# power.net
KiCad netlist of a schematic drawn in EAGLE
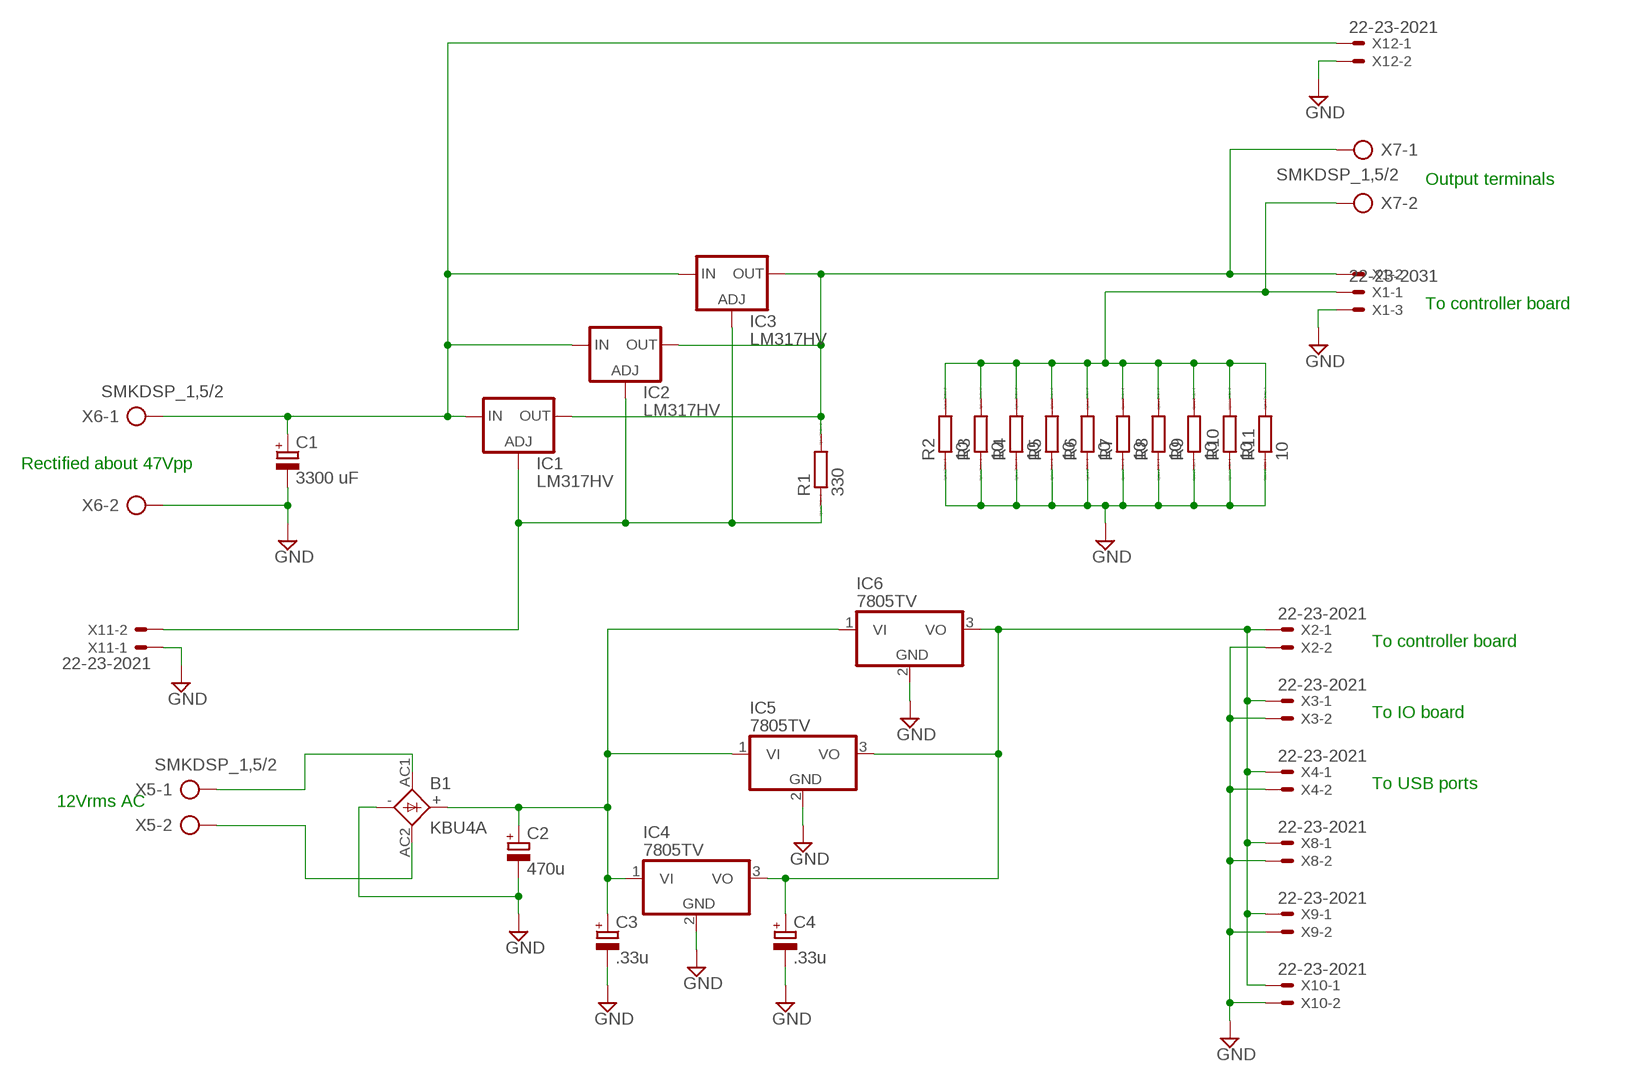
[diagram p0: schematic, sheet 1]

(export (version "E")
  (design (tool "Eeschema 10.0.6"))
  (components
    (comp (ref "B1")
      (value "KBU4A")
      (footprint "eagle-import:2KBB-R")
      (libsource (lib "eagle-import") (part "2KBB-R"))
    )
    (comp (ref "C1")
      (value "3300 uF")
      (footprint "eagle-import:EB25D")
      (libsource (lib "eagle-import") (part "CPOL-EUE10-25"))
    )
    (comp (ref "C2")
      (value "470u")
      (footprint "eagle-import:E5-10,5")
      (libsource (lib "eagle-import") (part "CPOL-EUE5-10.5"))
    )
    (comp (ref "C3")
      (value ".33u")
      (footprint "eagle-import:E2-5")
      (libsource (lib "eagle-import") (part "CPOL-EUE2-5"))
    )
    (comp (ref "C4")
      (value ".33u")
      (footprint "eagle-import:E2-5")
      (libsource (lib "eagle-import") (part "CPOL-EUE2-5"))
    )
    (comp (ref "IC1")
      (value "LM317HV")
      (footprint "eagle-import:317TS")
      (libsource (lib "eagle-import") (part "LM317TS"))
    )
    (comp (ref "IC2")
      (value "LM317HV")
      (footprint "eagle-import:317TS")
      (libsource (lib "eagle-import") (part "LM317TS"))
    )
    (comp (ref "IC3")
      (value "LM317HV")
      (footprint "eagle-import:317TS")
      (libsource (lib "eagle-import") (part "LM317TS"))
    )
    (comp (ref "IC4")
      (value "7805TV")
      (footprint "eagle-import:TO220V")
      (libsource (lib "eagle-import") (part "78TV05"))
    )
    (comp (ref "IC5")
      (value "7805TV")
      (footprint "eagle-import:TO220V")
      (libsource (lib "eagle-import") (part "78TV05"))
    )
    (comp (ref "IC6")
      (value "7805TV")
      (footprint "eagle-import:TO220V")
      (libsource (lib "eagle-import") (part "78TV05"))
    )
    (comp (ref "R1")
      (value "330")
      (footprint "eagle-import:0207_7")
      (libsource (lib "eagle-import") (part "R-EU_0207_7"))
    )
    (comp (ref "R2")
      (value "10")
      (footprint "eagle-import:0204_7")
      (libsource (lib "eagle-import") (part "R-EU_0204_7"))
    )
    (comp (ref "R3")
      (value "10")
      (footprint "eagle-import:0204_7")
      (libsource (lib "eagle-import") (part "R-EU_0204_7"))
    )
    (comp (ref "R4")
      (value "10")
      (footprint "eagle-import:0204_7")
      (libsource (lib "eagle-import") (part "R-EU_0204_7"))
    )
    (comp (ref "R5")
      (value "10")
      (footprint "eagle-import:0204_7")
      (libsource (lib "eagle-import") (part "R-EU_0204_7"))
    )
    (comp (ref "R6")
      (value "10")
      (footprint "eagle-import:0204_7")
      (libsource (lib "eagle-import") (part "R-EU_0204_7"))
    )
    (comp (ref "R7")
      (value "10")
      (footprint "eagle-import:0204_7")
      (libsource (lib "eagle-import") (part "R-EU_0204_7"))
    )
    (comp (ref "R8")
      (value "10")
      (footprint "eagle-import:0204_7")
      (libsource (lib "eagle-import") (part "R-EU_0204_7"))
    )
    (comp (ref "R9")
      (value "10")
      (footprint "eagle-import:0204_7")
      (libsource (lib "eagle-import") (part "R-EU_0204_7"))
    )
    (comp (ref "R10")
      (value "10")
      (footprint "eagle-import:0204_7")
      (libsource (lib "eagle-import") (part "R-EU_0204_7"))
    )
    (comp (ref "R11")
      (value "10")
      (footprint "eagle-import:0204_7")
      (libsource (lib "eagle-import") (part "R-EU_0204_7"))
    )
    (comp (ref "X1")
      (value "22-23-2031")
      (footprint "eagle-import:22-23-2031")
      (fields (field (name "MF") "MOLEX"))
      (libsource (lib "eagle-import") (part "22-23-2031"))
    )
    (comp (ref "X2")
      (value "22-23-2021")
      (footprint "eagle-import:22-23-2021")
      (fields (field (name "MF") "MOLEX"))
      (libsource (lib "eagle-import") (part "22-23-2021"))
    )
    (comp (ref "X3")
      (value "22-23-2021")
      (footprint "eagle-import:22-23-2021")
      (fields (field (name "MF") "MOLEX"))
      (libsource (lib "eagle-import") (part "22-23-2021"))
    )
    (comp (ref "X4")
      (value "22-23-2021")
      (footprint "eagle-import:22-23-2021")
      (fields (field (name "MF") "MOLEX"))
      (libsource (lib "eagle-import") (part "22-23-2021"))
    )
    (comp (ref "X5")
      (value "SMKDSP_1,5/2")
      (footprint "eagle-import:SMKDSP_1,5_2")
      (fields (field (name "MF") "FARNELL") (field (name "MPN") "1733570"))
      (libsource (lib "eagle-import") (part "SMKDSP_1,5/2"))
    )
    (comp (ref "X6")
      (value "SMKDSP_1,5/2")
      (footprint "eagle-import:SMKDSP_1,5_2")
      (fields (field (name "MF") "FARNELL") (field (name "MPN") "1733570"))
      (libsource (lib "eagle-import") (part "SMKDSP_1,5/2"))
    )
    (comp (ref "X7")
      (value "SMKDSP_1,5/2")
      (footprint "eagle-import:SMKDSP_1,5_2")
      (fields (field (name "MF") "FARNELL") (field (name "MPN") "1733570"))
      (libsource (lib "eagle-import") (part "SMKDSP_1,5/2"))
    )
    (comp (ref "X8")
      (value "22-23-2021")
      (footprint "eagle-import:22-23-2021")
      (fields (field (name "MF") "MOLEX"))
      (libsource (lib "eagle-import") (part "22-23-2021"))
    )
    (comp (ref "X9")
      (value "22-23-2021")
      (footprint "eagle-import:22-23-2021")
      (fields (field (name "MF") "MOLEX"))
      (libsource (lib "eagle-import") (part "22-23-2021"))
    )
    (comp (ref "X10")
      (value "22-23-2021")
      (footprint "eagle-import:22-23-2021")
      (fields (field (name "MF") "MOLEX"))
      (libsource (lib "eagle-import") (part "22-23-2021"))
    )
    (comp (ref "X11")
      (value "22-23-2021")
      (footprint "eagle-import:22-23-2021")
      (fields (field (name "MF") "MOLEX"))
      (libsource (lib "eagle-import") (part "22-23-2021"))
    )
    (comp (ref "X12")
      (value "22-23-2021")
      (footprint "eagle-import:22-23-2021")
      (fields (field (name "MF") "MOLEX"))
      (libsource (lib "eagle-import") (part "22-23-2021"))
    )
  )
  (nets
    (net (code "1") (name "GND") (class "Default")
      (node (ref "B1") (pin "-") (pinfunction "-_-") (pintype "passive"))
      (node (ref "C1") (pin "-") (pinfunction "-_-") (pintype "passive"))
      (node (ref "C2") (pin "-") (pinfunction "-_-") (pintype "passive"))
      (node (ref "C3") (pin "-") (pinfunction "-_-") (pintype "passive"))
      (node (ref "C4") (pin "-") (pinfunction "-_-") (pintype "passive"))
      (node (ref "IC4") (pin "2") (pinfunction "GND_2") (pintype "passive"))
      (node (ref "IC5") (pin "2") (pinfunction "GND_2") (pintype "passive"))
      (node (ref "IC6") (pin "2") (pinfunction "GND_2") (pintype "passive"))
      (node (ref "R10") (pin "1") (pinfunction "1_1") (pintype "passive"))
      (node (ref "R11") (pin "1") (pinfunction "1_1") (pintype "passive"))
      (node (ref "R2") (pin "1") (pinfunction "1_1") (pintype "passive"))
      (node (ref "R3") (pin "1") (pinfunction "1_1") (pintype "passive"))
      (node (ref "R4") (pin "1") (pinfunction "1_1") (pintype "passive"))
      (node (ref "R5") (pin "1") (pinfunction "1_1") (pintype "passive"))
      (node (ref "R6") (pin "1") (pinfunction "1_1") (pintype "passive"))
      (node (ref "R7") (pin "1") (pinfunction "1_1") (pintype "passive"))
      (node (ref "R8") (pin "1") (pinfunction "1_1") (pintype "passive"))
      (node (ref "R9") (pin "1") (pinfunction "1_1") (pintype "passive"))
      (node (ref "X1") (pin "3") (pinfunction "S_3") (pintype "passive"))
      (node (ref "X10") (pin "2") (pinfunction "S_2") (pintype "passive"))
      (node (ref "X11") (pin "1") (pinfunction "S_1") (pintype "passive"))
      (node (ref "X12") (pin "2") (pinfunction "S_2") (pintype "passive"))
      (node (ref "X2") (pin "2") (pinfunction "S_2") (pintype "passive"))
      (node (ref "X3") (pin "2") (pinfunction "S_2") (pintype "passive"))
      (node (ref "X4") (pin "2") (pinfunction "S_2") (pintype "passive"))
      (node (ref "X6") (pin "2") (pinfunction "KL_2") (pintype "passive"))
      (node (ref "X8") (pin "2") (pinfunction "S_2") (pintype "passive"))
      (node (ref "X9") (pin "2") (pinfunction "S_2") (pintype "passive"))
    )
    (net (code "2") (name "Net-(IC1-ADJ)") (class "Default")
      (node (ref "IC1") (pin "1") (pinfunction "ADJ_1") (pintype "input"))
      (node (ref "IC2") (pin "1") (pinfunction "ADJ_1") (pintype "input"))
      (node (ref "IC3") (pin "1") (pinfunction "ADJ_1") (pintype "input"))
      (node (ref "R1") (pin "1") (pinfunction "1_1") (pintype "passive"))
      (node (ref "X11") (pin "2") (pinfunction "S_2") (pintype "passive"))
    )
    (net (code "3") (name "Net-(IC1-IN)") (class "Default")
      (node (ref "C1") (pin "+") (pinfunction "+_+") (pintype "passive"))
      (node (ref "IC1") (pin "3") (pinfunction "IN_3") (pintype "input"))
      (node (ref "IC2") (pin "3") (pinfunction "IN_3") (pintype "input"))
      (node (ref "IC3") (pin "3") (pinfunction "IN_3") (pintype "input"))
      (node (ref "X12") (pin "1") (pinfunction "S_1") (pintype "passive"))
      (node (ref "X6") (pin "1") (pinfunction "KL_1") (pintype "passive"))
    )
    (net (code "4") (name "Net-(IC1-OUT)") (class "Default")
      (node (ref "IC1") (pin "2") (pinfunction "OUT_2") (pintype "passive"))
      (node (ref "IC2") (pin "2") (pinfunction "OUT_2") (pintype "passive"))
      (node (ref "IC3") (pin "2") (pinfunction "OUT_2") (pintype "passive"))
      (node (ref "R1") (pin "2") (pinfunction "2_2") (pintype "passive"))
      (node (ref "X1") (pin "2") (pinfunction "S_2") (pintype "passive"))
      (node (ref "X7") (pin "1") (pinfunction "KL_1") (pintype "passive"))
    )
    (net (code "5") (name "Net-(IC4-VI)") (class "Default")
      (node (ref "B1") (pin "+") (pinfunction "+_+") (pintype "passive"))
      (node (ref "C2") (pin "+") (pinfunction "+_+") (pintype "passive"))
      (node (ref "C3") (pin "+") (pinfunction "+_+") (pintype "passive"))
      (node (ref "IC4") (pin "1") (pinfunction "VI_1") (pintype "input"))
      (node (ref "IC5") (pin "1") (pinfunction "VI_1") (pintype "input"))
      (node (ref "IC6") (pin "1") (pinfunction "VI_1") (pintype "input"))
    )
    (net (code "6") (name "Net-(IC4-VO)") (class "Default")
      (node (ref "C4") (pin "+") (pinfunction "+_+") (pintype "passive"))
      (node (ref "IC4") (pin "3") (pinfunction "VO_3") (pintype "passive"))
      (node (ref "IC5") (pin "3") (pinfunction "VO_3") (pintype "passive"))
      (node (ref "IC6") (pin "3") (pinfunction "VO_3") (pintype "passive"))
      (node (ref "X10") (pin "1") (pinfunction "S_1") (pintype "passive"))
      (node (ref "X2") (pin "1") (pinfunction "S_1") (pintype "passive"))
      (node (ref "X3") (pin "1") (pinfunction "S_1") (pintype "passive"))
      (node (ref "X4") (pin "1") (pinfunction "S_1") (pintype "passive"))
      (node (ref "X8") (pin "1") (pinfunction "S_1") (pintype "passive"))
      (node (ref "X9") (pin "1") (pinfunction "S_1") (pintype "passive"))
    )
    (net (code "7") (name "Net-(X1A-S)") (class "Default")
      (node (ref "R10") (pin "2") (pinfunction "2_2") (pintype "passive"))
      (node (ref "R11") (pin "2") (pinfunction "2_2") (pintype "passive"))
      (node (ref "R2") (pin "2") (pinfunction "2_2") (pintype "passive"))
      (node (ref "R3") (pin "2") (pinfunction "2_2") (pintype "passive"))
      (node (ref "R4") (pin "2") (pinfunction "2_2") (pintype "passive"))
      (node (ref "R5") (pin "2") (pinfunction "2_2") (pintype "passive"))
      (node (ref "R6") (pin "2") (pinfunction "2_2") (pintype "passive"))
      (node (ref "R7") (pin "2") (pinfunction "2_2") (pintype "passive"))
      (node (ref "R8") (pin "2") (pinfunction "2_2") (pintype "passive"))
      (node (ref "R9") (pin "2") (pinfunction "2_2") (pintype "passive"))
      (node (ref "X1") (pin "1") (pinfunction "S_1") (pintype "passive"))
      (node (ref "X7") (pin "2") (pinfunction "KL_2") (pintype "passive"))
    )
    (net (code "8") (name "Net-(X5A-KL)") (class "Default")
      (node (ref "B1") (pin "AC1") (pinfunction "AC1_AC1") (pintype "passive"))
      (node (ref "X5") (pin "1") (pinfunction "KL_1") (pintype "passive"))
    )
    (net (code "9") (name "Net-(X5B-KL)") (class "Default")
      (node (ref "B1") (pin "AC2") (pinfunction "AC2_AC2") (pintype "passive"))
      (node (ref "X5") (pin "2") (pinfunction "KL_2") (pintype "passive"))
    )
  )
)
